# Power-Sheet.net
KiCad netlist of a schematic drawn in Altium Designer
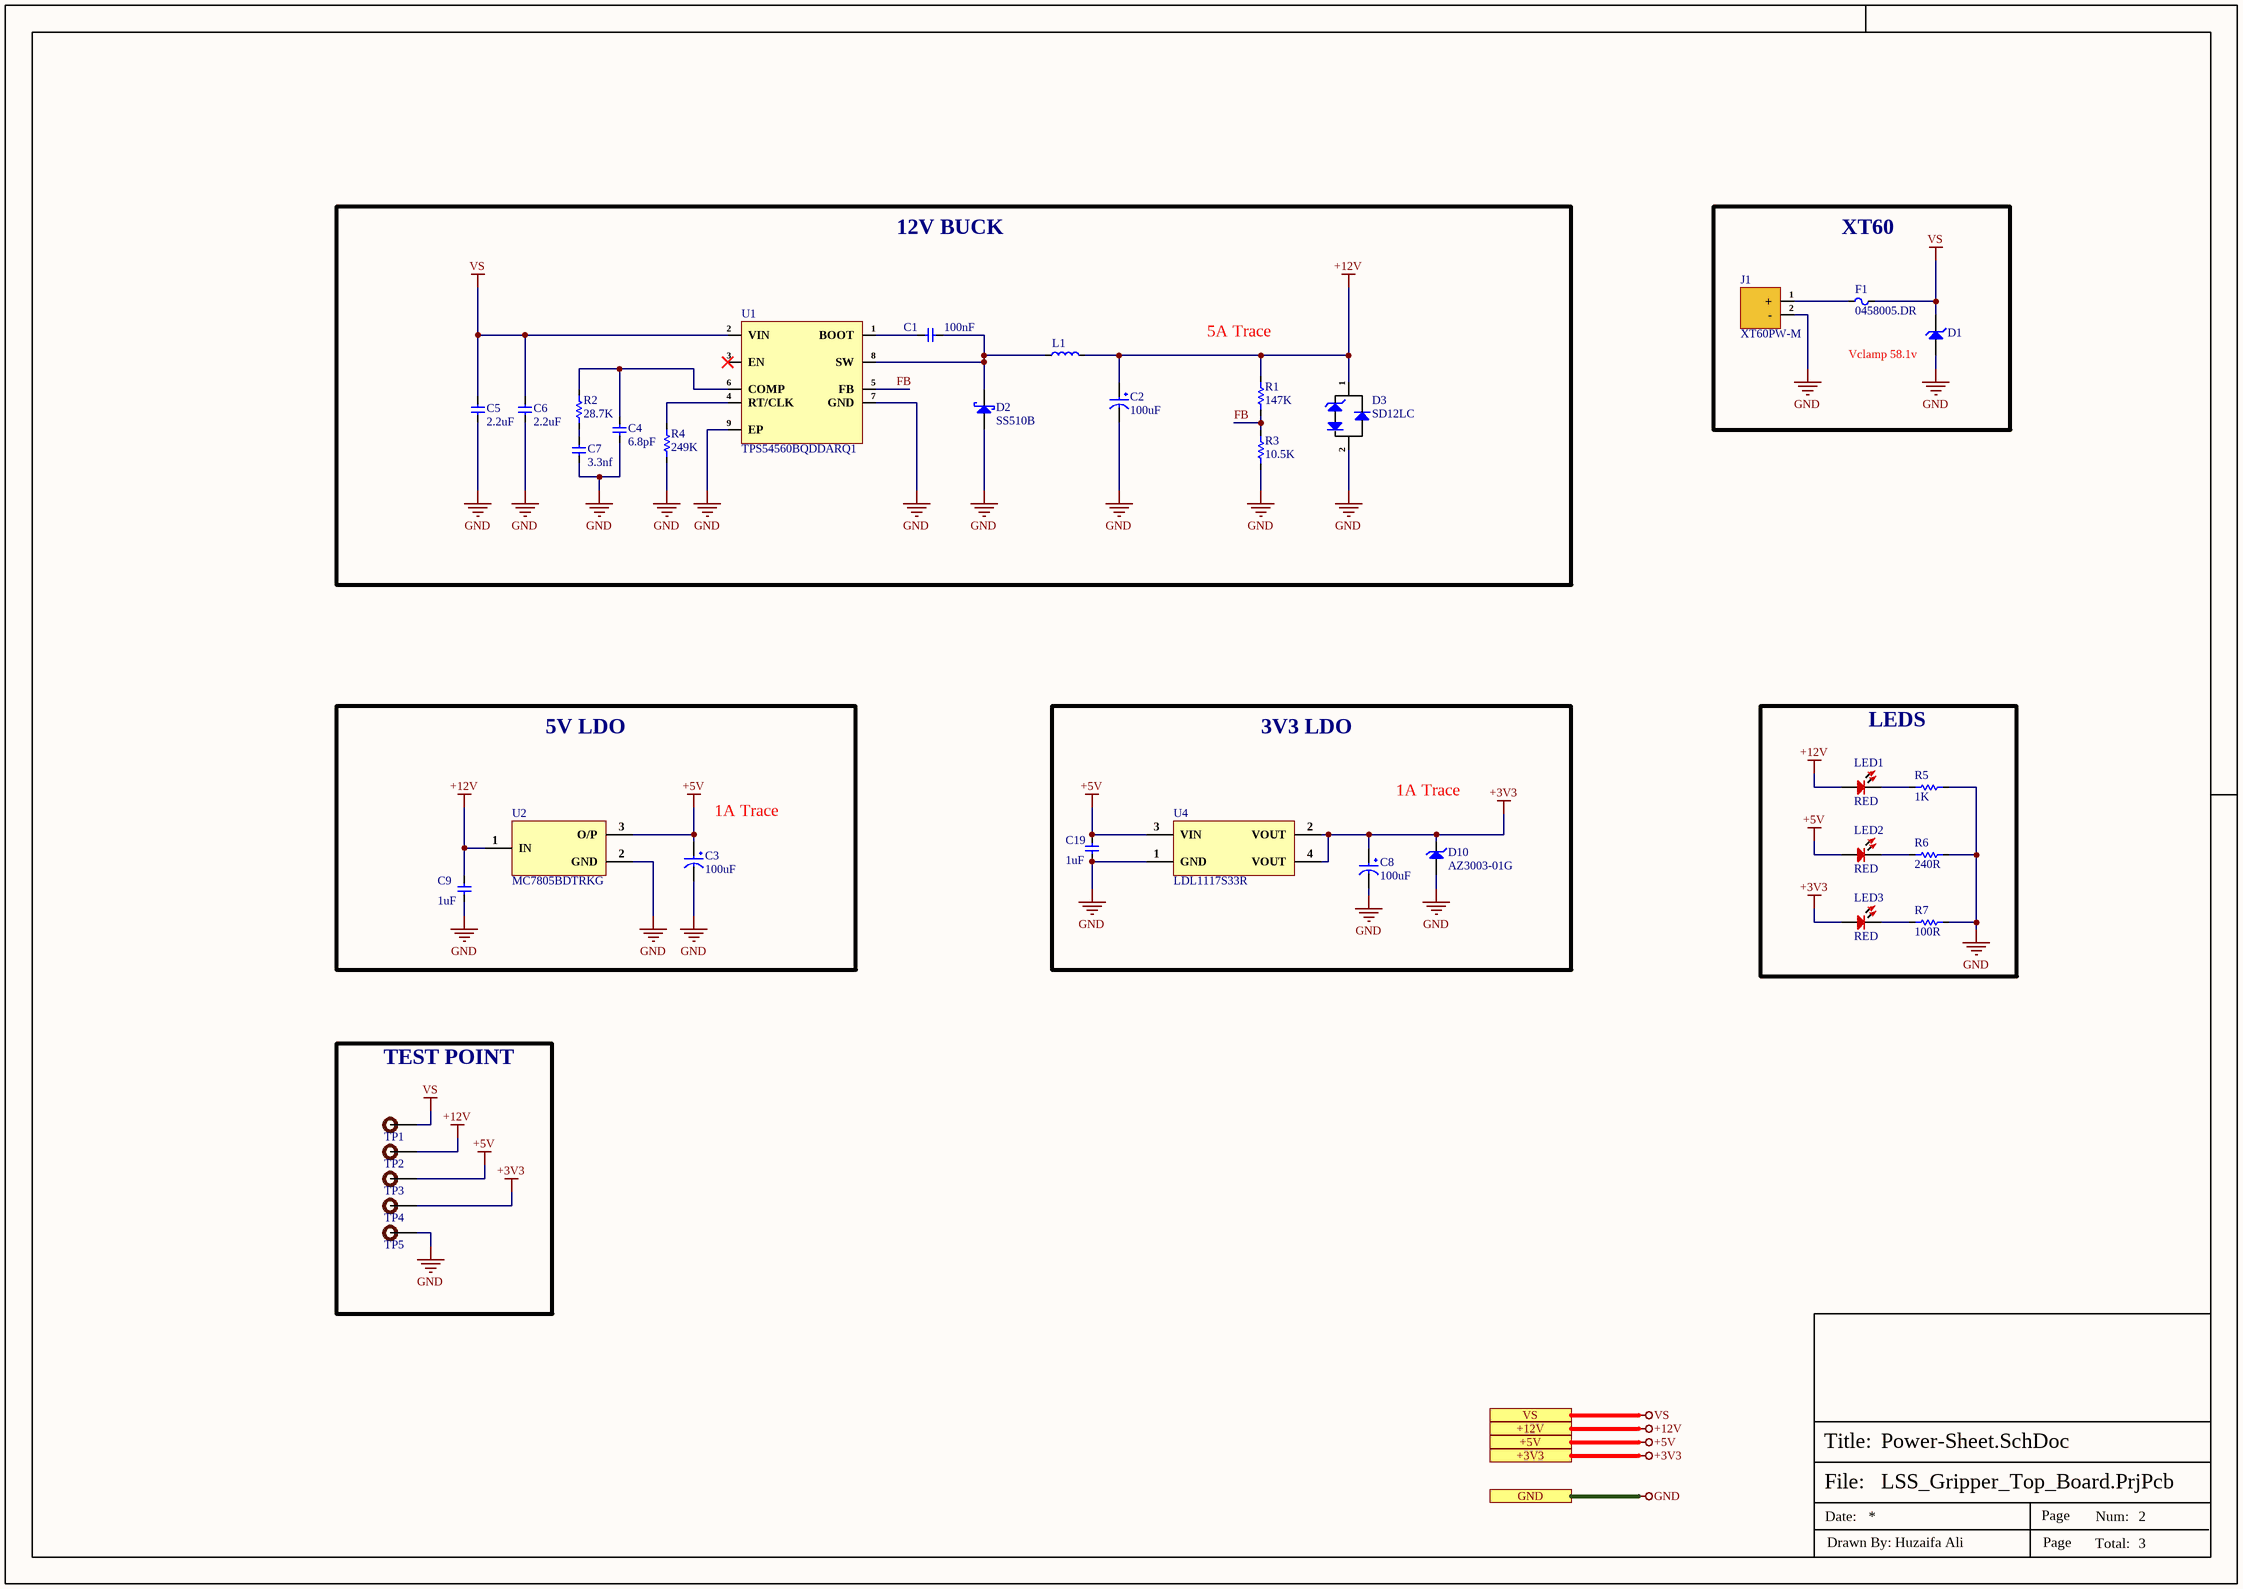
[diagram p0: Power-Sheet.SchDoc]

(export (version "E")
  (design (tool "Eeschema 10.0.6"))
  (components
    (comp (ref "C1")
      (value "100nF")
      (footprint "cap-0402")
      (description "CAP CER 0.1UF 50V X7R 0402")
      (fields
        (field (name "MANUFACTURER") "TDK")
        (field (name "MANUFACTURER PART NUMBER") "C1005X7R1H104KT000F")
      )
      (libsource (lib "eSpark Libraries") (part "C1005X7R1H104KT000F"))
    )
    (comp (ref "C2")
      (value "100uF")
      (footprint "Case-E")
      (description "CAP TANT 100UF 20% 25V 2917")
      (fields
        (field (name "MANUFACTURER") "Kyocera AVX")
        (field (name "MANUFACTURER PART NUMBER") "TAJE107M025RNJ")
      )
      (libsource (lib "eSpark Libraries") (part "TAJE107M025RNJ"))
    )
    (comp (ref "C3")
      (value "100uF")
      (footprint "Case-E")
      (description "CAP TANT 100UF 20% 25V 2917")
      (fields
        (field (name "MANUFACTURER") "Kyocera AVX")
        (field (name "MANUFACTURER PART NUMBER") "TAJE107M025RNJ")
      )
      (libsource (lib "eSpark Libraries") (part "TAJE107M025RNJ"))
    )
    (comp (ref "C4")
      (value "6.8pF")
      (footprint "Cap-0402")
      (description "CAP CER 6.8PF 50V C0G/NPO 0402")
      (fields
        (field (name "MANUFACTURER") "Yageo")
        (field (name "MANUFACTURER PART NUMBER") "CC0402CRNPO9BN6R8")
      )
      (libsource (lib "eSpark Libraries") (part "CC0402CRNPO9BN6R8"))
    )
    (comp (ref "C5")
      (value "2.2uF")
      (footprint "Cap-0805")
      (description "CAP CER 2.2UF 100V X7T 0805")
      (fields
        (field (name "MANUFACTURER") "Murata")
        (field (name "MANUFACTURER PART NUMBER") "GRM21BD72A225KE01L")
      )
      (libsource (lib "eSpark Libraries") (part "GRM21BD72A225KE01L"))
    )
    (comp (ref "C6")
      (value "2.2uF")
      (footprint "Cap-0805")
      (description "CAP CER 2.2UF 100V X7T 0805")
      (fields
        (field (name "MANUFACTURER") "Murata")
        (field (name "MANUFACTURER PART NUMBER") "GRM21BD72A225KE01L")
      )
      (libsource (lib "eSpark Libraries") (part "GRM21BD72A225KE01L"))
    )
    (comp (ref "C7")
      (value "3.3nf")
      (footprint "Cap-0402")
      (description "CAP CER 3.3nF 50V X7R 0402")
      (fields
        (field (name "MANUFACTURER") "Yageo")
        (field (name "MANUFACTURER PART NUMBER") "CC0402KRX7R9BB332")
      )
      (libsource (lib "eSpark Libraries") (part "CC0402KRX7R9BB332"))
    )
    (comp (ref "C8")
      (value "100uF")
      (footprint "Case-E")
      (description "CAP TANT 100UF 20% 25V 2917")
      (fields
        (field (name "MANUFACTURER") "Kyocera AVX")
        (field (name "MANUFACTURER PART NUMBER") "TAJE107M025RNJ")
      )
      (libsource (lib "eSpark Libraries") (part "TAJE107M025RNJ"))
    )
    (comp (ref "C9")
      (value "1uF")
      (footprint "Cap-0603")
      (description "CAP CER 1UF 25V X5R 0603")
      (fields
        (field (name "MANUFACTURER") "Yageo")
        (field (name "MANUFACTURER PART NUMBER") "CC0603KRX5R8BB105")
      )
      (libsource (lib "eSpark Libraries") (part "CC0603KRX5R8BB105"))
    )
    (comp (ref "C19")
      (value "1uF")
      (footprint "Cap-0603")
      (description "CAP CER 1UF 25V X5R 0603")
      (fields
        (field (name "MANUFACTURER") "Yageo")
        (field (name "MANUFACTURER PART NUMBER") "CC0603KRX5R8BB105")
      )
      (libsource (lib "eSpark Libraries") (part "CC0603KRX5R8BB105"))
    )
    (comp (ref "D1")
      (value "AZ4036-01G")
      (footprint "SOD-123")
      (description "Clamp Ipp Tvs Diode Surface Mount SOD-123")
      (fields (field (name "MANUFACTURER") "Amazing"))
      (libsource (lib "eSpark Libraries") (part "AZ4036-01G"))
    )
    (comp (ref "D2")
      (value "SS510B")
      (footprint "SMB_")
      (description "SCHOTTKY DIODE SMB 100V 5A")
      (fields (field (name "MANUFACTURER") "MDD") (field (name "LCSC PART NUMBER") "C3011128"))
      (libsource (lib "eSpark Libraries") (part "SS510B"))
    )
    (comp (ref "D3")
      (value "SD12LC")
      (footprint "SOD-323")
      (description "TVS DIODE 12VWM 28.6VC SOD323")
      (fields (field (name "MANUFACTURER") "Sangdest Microelectronics"))
      (libsource (lib "eSpark Libraries") (part "SD12LC"))
    )
    (comp (ref "D10")
      (value "AZ3003-01G")
      (footprint "SOD-123")
      (description "TVS SURGE PROTECTOR 1-CH 3.3V")
      (fields (field (name "MANUFACTURER") "Amazing"))
      (libsource (lib "eSpark Libraries") (part "AZ3003-01G"))
    )
    (comp (ref "F1")
      (value "0458005.DR")
      (footprint "Fuse 1206 (3216 Metric)")
      (description "FUSE BRD MNT 5A 32VAC 75VDC 1206")
      (fields (field (name "MANUFACTURER") "Littelfuse") (field (name "LCSC PART NUMBER") "C187561"))
      (libsource (lib "eSpark Libraries") (part "0458005.DR"))
    )
    (comp (ref "J1")
      (value "XT60PW-M")
      (footprint "XT60PW-M")
      (description "Power Connectors ROHS")
      (fields (field (name "MANUFACTURER") "Changzhou Amass Elec") (field (name "LCSC PART NUMBER") "C98732"))
      (libsource (lib "eSpark Libraries") (part "XT60PW-M"))
    )
    (comp (ref "L1")
      (value "CXP1050-220M-AG(22uh)")
      (footprint "CXP1050-220M-AG(22uh)")
      (description "5.5A 22uH Molding Choke ±20% 8A 1050 Power Inductors ROHS")
      (fields (field (name "MANUFACTURER") "DMBJ") (field (name "LCSC PART NUMBER") "C7461393"))
      (libsource (lib "eSpark Libraries") (part "CXP1050-220M-AG(22uh)"))
    )
    (comp (ref "LED1")
      (value "RED")
      (footprint "LED-0603")
      (description "RED LED 0603 Light Emitting Diodes")
      (fields
        (field (name "MANUFACTURER") "Foshan NationStar Optoelectronics")
        (field (name "MANUFACTURER PART NUMBER") "NCD0603R3")
      )
      (libsource (lib "eSpark Libraries") (part "NCD0603R3"))
    )
    (comp (ref "LED2")
      (value "RED")
      (footprint "LED-0603")
      (description "RED LED 0603 Light Emitting Diodes")
      (fields
        (field (name "MANUFACTURER") "Foshan NationStar Optoelectronics")
        (field (name "MANUFACTURER PART NUMBER") "NCD0603R3")
      )
      (libsource (lib "eSpark Libraries") (part "NCD0603R3"))
    )
    (comp (ref "LED3")
      (value "RED")
      (footprint "LED-0603")
      (description "RED LED 0603 Light Emitting Diodes")
      (fields
        (field (name "MANUFACTURER") "Foshan NationStar Optoelectronics")
        (field (name "MANUFACTURER PART NUMBER") "NCD0603R3")
      )
      (libsource (lib "eSpark Libraries") (part "NCD0603R3"))
    )
    (comp (ref "R1")
      (value "147K")
      (footprint "Res-0402")
      (description "RES 147K OHM 1% 1/16W 0402")
      (fields
        (field (name "MANUFACTURER") "Yageo")
        (field (name "MANUFACTURER PART NUMBER") "RC0402FR-07147KL")
      )
      (libsource (lib "eSpark Libraries") (part "RC0402FR-07147KL"))
    )
    (comp (ref "R2")
      (value "28.7K")
      (footprint "Res-0402")
      (description "62.5mW 100V ±1% 28.7kΩ 0402 Chip Resistor - Surface Mount ROHS")
      (fields
        (field (name "MANUFACTURER") "Royal Ohm")
        (field (name "MANUFACTURER PART NUMBER") "NQ02WGF2872TCE")
      )
      (libsource (lib "eSpark Libraries") (part "NQ02WGF2872TCE"))
    )
    (comp (ref "R3")
      (value "10.5K")
      (footprint "Res-0402")
      (description "RES SMD 10.5K OHM 1% 1/16W 0402")
      (fields
        (field (name "MANUFACTURER") "Vishay")
        (field (name "MANUFACTURER PART NUMBER") "CRCW040210K5FKED")
      )
      (libsource (lib "eSpark Libraries") (part "CRCW040210K5FKED"))
    )
    (comp (ref "R4")
      (value "249K")
      (footprint "Res-0402")
      (description "62.5mW Thick Film Resistors 50V ±100ppm/℃ ±1% 249kΩ 0402 Chip Resistor - Surface Mount ROHS")
      (fields
        (field (name "MANUFACTURER") "Royal Electronic Factory")
        (field (name "MANUFACTURER PART NUMBER") "0402WGF2493TCE")
      )
      (libsource (lib "eSpark Libraries") (part "0402WGF2493TCE"))
    )
    (comp (ref "R5")
      (value "1K")
      (footprint "Res-0402")
      (description "RES 1K OHM 1% 1/16W 0402")
      (fields
        (field (name "MANUFACTURER") "Yageo")
        (field (name "MANUFACTURER PART NUMBER") "RC0402FR-071KL")
      )
      (libsource (lib "eSpark Libraries") (part "RC0402FR-071KL"))
    )
    (comp (ref "R6")
      (value "240R")
      (footprint "Res-0402")
      (description "RES 240 OHM 1% 1/16W 0402")
      (fields
        (field (name "MANUFACTURER") "Yageo")
        (field (name "MANUFACTURER PART NUMBER") "RC0402FR-07240RL")
      )
      (libsource (lib "eSpark Libraries") (part "RC0402FR-07240RL"))
    )
    (comp (ref "R7")
      (value "100R")
      (footprint "Res-0402")
      (description "RES 100 OHM 1% 1/16W 0402")
      (fields
        (field (name "MANUFACTURER") "Yageo")
        (field (name "MANUFACTURER PART NUMBER") "RC0402FR-07100RL")
      )
      (libsource (lib "eSpark Libraries") (part "RC0402FR-07100RL"))
    )
    (comp (ref "TP1")
      (value "TEST POINT")
      (footprint "Test-point")
      (description "Test Point ON")
      (libsource (lib "eSpark Libraries") (part "TEST POINT"))
    )
    (comp (ref "TP2")
      (value "TEST POINT")
      (footprint "Test-point")
      (description "Test Point ON")
      (libsource (lib "eSpark Libraries") (part "TEST POINT"))
    )
    (comp (ref "TP3")
      (value "TEST POINT")
      (footprint "Test-point")
      (description "Test Point ON")
      (libsource (lib "eSpark Libraries") (part "TEST POINT"))
    )
    (comp (ref "TP4")
      (value "TEST POINT")
      (footprint "Test-point")
      (description "Test Point ON")
      (libsource (lib "eSpark Libraries") (part "TEST POINT"))
    )
    (comp (ref "TP5")
      (value "TEST POINT")
      (footprint "Test-point")
      (description "Test Point ON")
      (libsource (lib "eSpark Libraries") (part "TEST POINT"))
    )
    (comp (ref "U1")
      (value "TPS54560BQDDARQ1")
      (footprint "8-SO PowerPad")
      (description "IC REG BCK SPLIT RAIL ADJ 8SOPWR")
      (fields (field (name "MANUFACTURER") "Texas Instruments") (field (name "LCSC PART NUMBER") "C2072188"))
      (libsource (lib "eSpark Libraries") (part "TPS54560BQDDARQ1"))
    )
    (comp (ref "U2")
      (value "MC7805BDTRKG")
      (footprint "DPAK_")
      (description "IC REG LINEAR 5V 1A DPAK")
      (fields (field (name "MANUFACTURER") "onsemi") (field (name "LCSC PART NUMBER") "C110908"))
      (libsource (lib "eSpark Libraries") (part "MC7805BDTRKG"))
    )
    (comp (ref "U4")
      (value "LDL1117S33R")
      (footprint "SOT- 223")
      (description "IC REG LINEAR 3.3V 1.2A SOT223")
      (fields (field (name "MANUFACTURER") "STMicroelectronics") (field (name "LCSC PART NUMBER") "C435835"))
      (libsource (lib "eSpark Libraries") (part "LDL1117S33R"))
    )
  )
  (nets
    (net (code "1") (name "+3V3") (class "Default")
      (node (ref "C8") (pin "1") (pinfunction "1_1") (pintype "passive"))
      (node (ref "D10") (pin "2") (pinfunction "K_2") (pintype "passive"))
      (node (ref "LED3") (pin "1") (pinfunction "1_1") (pintype "passive"))
      (node (ref "TP4") (pin "1") (pinfunction "1_1") (pintype "passive"))
      (node (ref "U4") (pin "2") (pinfunction "VOUT_2") (pintype "passive"))
      (node (ref "U4") (pin "4") (pinfunction "VOUT_4") (pintype "passive"))
    )
    (net (code "2") (name "+5V") (class "Default")
      (node (ref "C19") (pin "2") (pinfunction "2_2") (pintype "passive"))
      (node (ref "C3") (pin "1") (pinfunction "1_1") (pintype "passive"))
      (node (ref "LED2") (pin "1") (pinfunction "1_1") (pintype "passive"))
      (node (ref "TP3") (pin "1") (pinfunction "1_1") (pintype "passive"))
      (node (ref "U2") (pin "3") (pinfunction "O/P_3") (pintype "passive"))
      (node (ref "U4") (pin "3") (pinfunction "VIN_3") (pintype "passive"))
    )
    (net (code "3") (name "+12V") (class "Default")
      (node (ref "C2") (pin "1") (pinfunction "1_1") (pintype "passive"))
      (node (ref "C9") (pin "2") (pinfunction "2_2") (pintype "passive"))
      (node (ref "D3") (pin "1") (pinfunction "K_1") (pintype "passive"))
      (node (ref "L1") (pin "2") (pinfunction "2_2") (pintype "passive"))
      (node (ref "LED1") (pin "1") (pinfunction "1_1") (pintype "passive"))
      (node (ref "R1") (pin "2") (pinfunction "2_2") (pintype "passive"))
      (node (ref "TP2") (pin "1") (pinfunction "1_1") (pintype "passive"))
      (node (ref "U2") (pin "1") (pinfunction "IN_1") (pintype "passive"))
    )
    (net (code "4") (name "/FB") (class "Default")
      (node (ref "R1") (pin "1") (pinfunction "1_1") (pintype "passive"))
      (node (ref "R3") (pin "2") (pinfunction "2_2") (pintype "passive"))
      (node (ref "U1") (pin "5") (pinfunction "FB_5") (pintype "passive"))
    )
    (net (code "5") (name "GND") (class "Default")
      (node (ref "C19") (pin "1") (pinfunction "1_1") (pintype "passive"))
      (node (ref "C2") (pin "2") (pinfunction "2_2") (pintype "passive"))
      (node (ref "C3") (pin "2") (pinfunction "2_2") (pintype "passive"))
      (node (ref "C4") (pin "1") (pinfunction "1_1") (pintype "passive"))
      (node (ref "C5") (pin "1") (pinfunction "1_1") (pintype "passive"))
      (node (ref "C6") (pin "1") (pinfunction "1_1") (pintype "passive"))
      (node (ref "C7") (pin "1") (pinfunction "1_1") (pintype "passive"))
      (node (ref "C8") (pin "2") (pinfunction "2_2") (pintype "passive"))
      (node (ref "C9") (pin "1") (pinfunction "1_1") (pintype "passive"))
      (node (ref "D1") (pin "1") (pinfunction "A_1") (pintype "passive"))
      (node (ref "D10") (pin "1") (pinfunction "A_1") (pintype "passive"))
      (node (ref "D2") (pin "1") (pinfunction "A_1") (pintype "passive"))
      (node (ref "D3") (pin "2") (pinfunction "A/K_2") (pintype "passive"))
      (node (ref "J1") (pin "2") (pinfunction "-_2") (pintype "passive"))
      (node (ref "R3") (pin "1") (pinfunction "1_1") (pintype "passive"))
      (node (ref "R4") (pin "1") (pinfunction "1_1") (pintype "passive"))
      (node (ref "R5") (pin "2") (pinfunction "2_2") (pintype "passive"))
      (node (ref "R6") (pin "2") (pinfunction "2_2") (pintype "passive"))
      (node (ref "R7") (pin "2") (pinfunction "2_2") (pintype "passive"))
      (node (ref "TP5") (pin "1") (pinfunction "1_1") (pintype "passive"))
      (node (ref "U1") (pin "7") (pinfunction "GND_7") (pintype "passive"))
      (node (ref "U1") (pin "9") (pinfunction "EP_9") (pintype "passive"))
      (node (ref "U2") (pin "2") (pinfunction "GND_2") (pintype "passive"))
      (node (ref "U4") (pin "1") (pinfunction "GND_1") (pintype "passive"))
    )
    (net (code "6") (name "Net-(C7-Pad2)") (class "Default")
      (node (ref "C7") (pin "2") (pinfunction "2_2") (pintype "passive"))
      (node (ref "R2") (pin "1") (pinfunction "1_1") (pintype "passive"))
    )
    (net (code "7") (name "Net-(D2-K)") (class "Default")
      (node (ref "C1") (pin "1") (pinfunction "1_1") (pintype "passive"))
      (node (ref "D2") (pin "2") (pinfunction "K_2") (pintype "passive"))
      (node (ref "L1") (pin "1") (pinfunction "1_1") (pintype "passive"))
      (node (ref "U1") (pin "8") (pinfunction "SW_8") (pintype "passive"))
    )
    (net (code "8") (name "Net-(J1-+)") (class "Default")
      (node (ref "F1") (pin "1") (pinfunction "1_1") (pintype "passive"))
      (node (ref "J1") (pin "1") (pinfunction "+_1") (pintype "passive"))
    )
    (net (code "9") (name "Net-(LED1-Pad2)") (class "Default")
      (node (ref "LED1") (pin "2") (pinfunction "2_2") (pintype "passive"))
      (node (ref "R5") (pin "1") (pinfunction "1_1") (pintype "passive"))
    )
    (net (code "10") (name "Net-(LED2-Pad2)") (class "Default")
      (node (ref "LED2") (pin "2") (pinfunction "2_2") (pintype "passive"))
      (node (ref "R6") (pin "1") (pinfunction "1_1") (pintype "passive"))
    )
    (net (code "11") (name "Net-(LED3-Pad2)") (class "Default")
      (node (ref "LED3") (pin "2") (pinfunction "2_2") (pintype "passive"))
      (node (ref "R7") (pin "1") (pinfunction "1_1") (pintype "passive"))
    )
    (net (code "12") (name "Net-(U1-BOOT)") (class "Default")
      (node (ref "C1") (pin "2") (pinfunction "2_2") (pintype "passive"))
      (node (ref "U1") (pin "1") (pinfunction "BOOT_1") (pintype "passive"))
    )
    (net (code "13") (name "Net-(U1-COMP)") (class "Default")
      (node (ref "C4") (pin "2") (pinfunction "2_2") (pintype "passive"))
      (node (ref "R2") (pin "2") (pinfunction "2_2") (pintype "passive"))
      (node (ref "U1") (pin "6") (pinfunction "COMP_6") (pintype "passive"))
    )
    (net (code "14") (name "Net-(U1-RT{slash}CLK)") (class "Default")
      (node (ref "R4") (pin "2") (pinfunction "2_2") (pintype "passive"))
      (node (ref "U1") (pin "4") (pinfunction "RT/CLK_4") (pintype "passive"))
    )
    (net (code "15") (name "VS") (class "Default")
      (node (ref "C5") (pin "2") (pinfunction "2_2") (pintype "passive"))
      (node (ref "C6") (pin "2") (pinfunction "2_2") (pintype "passive"))
      (node (ref "D1") (pin "2") (pinfunction "K_2") (pintype "passive"))
      (node (ref "F1") (pin "2") (pinfunction "2_2") (pintype "passive"))
      (node (ref "TP1") (pin "1") (pinfunction "1_1") (pintype "passive"))
      (node (ref "U1") (pin "2") (pinfunction "VIN_2") (pintype "passive"))
    )
    (net (code "16") (name "unconnected-(U1-EN-Pad3)") (class "Default")
      (node (ref "U1") (pin "3") (pinfunction "EN_3") (pintype "passive+no_connect"))
    )
  )
)
